# ENERGIS_DispBrd_Rack-PDU_1_0_3.net
KiCad netlist of a schematic drawn in EAGLE
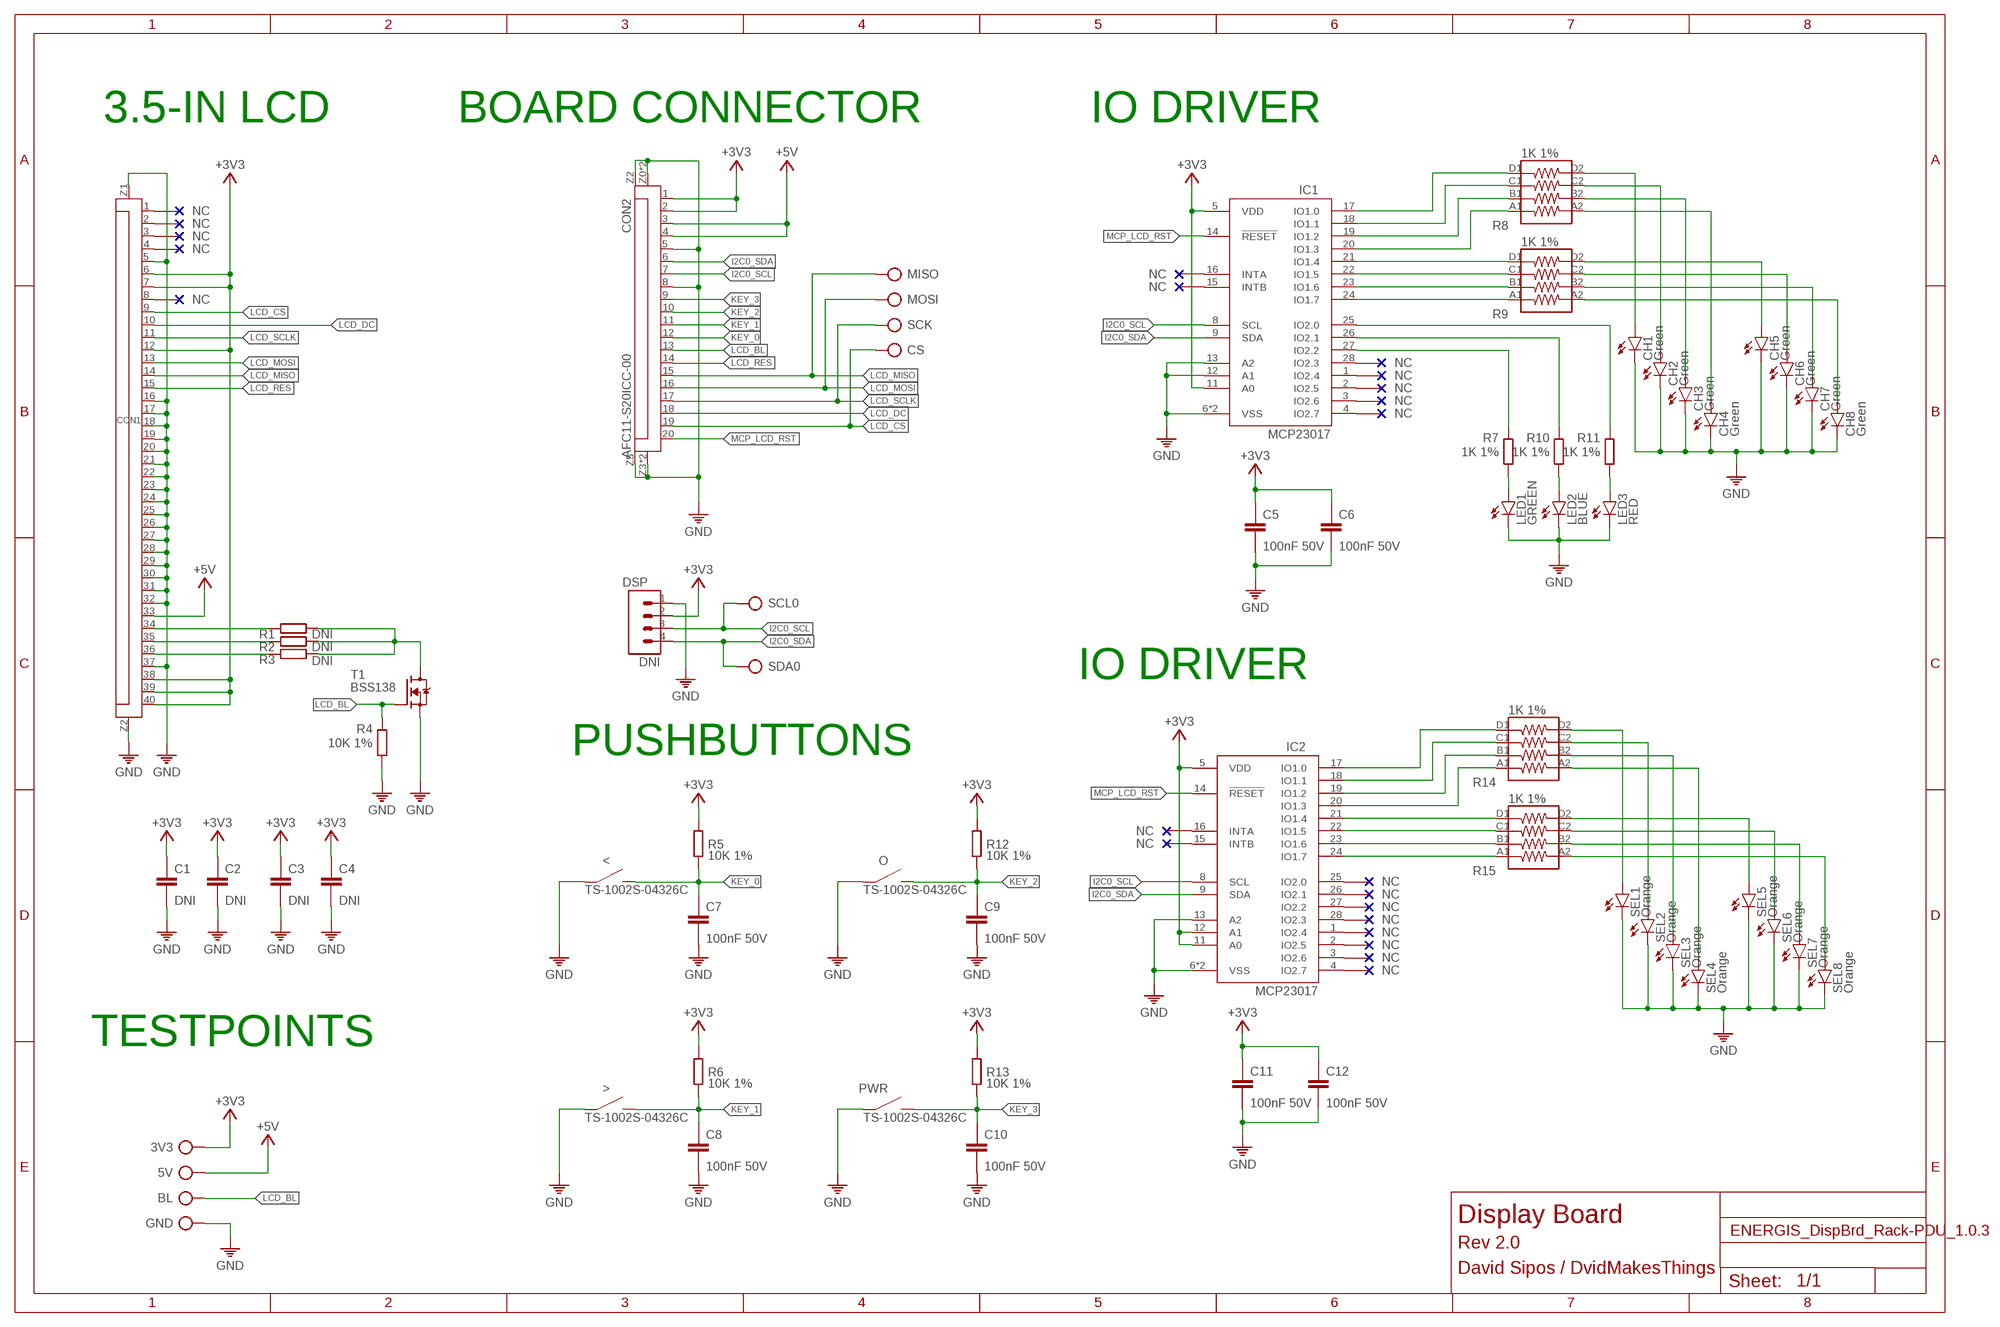
[diagram p0: schematic, sheet 1]

(export (version "E")
  (design (tool "Eeschema 10.0.6"))
  (components
    (comp (ref "3V3") (value "TP") (footprint "eagle-import:TP") (libsource (lib "eagle-import") (part "TP")))
    (comp (ref "5V") (value "TP") (footprint "eagle-import:TP") (libsource (lib "eagle-import") (part "TP")))
    (comp (ref "<")
      (value "TS-1002S-04326C")
      (footprint "eagle-import:PUSHBUTTON-6X6")
      (fields (field (name "LCSC_PART") "C455108"))
      (libsource (lib "eagle-import") (part "SWITCH6X6-SHORT"))
    )
    (comp (ref ">")
      (value "TS-1002S-04326C")
      (footprint "eagle-import:PUSHBUTTON-6X6")
      (fields (field (name "LCSC_PART") "C455108"))
      (libsource (lib "eagle-import") (part "SWITCH6X6-SHORT"))
    )
    (comp (ref "BL") (value "TP") (footprint "eagle-import:TP") (libsource (lib "eagle-import") (part "TP")))
    (comp (ref "C1")
      (value "DNI")
      (footprint "eagle-import:C0402")
      (libsource (lib "eagle-import") (part "C-0402"))
    )
    (comp (ref "C2")
      (value "DNI")
      (footprint "eagle-import:C0402")
      (libsource (lib "eagle-import") (part "C-0402"))
    )
    (comp (ref "C3")
      (value "DNI")
      (footprint "eagle-import:C0402")
      (libsource (lib "eagle-import") (part "C-0402"))
    )
    (comp (ref "C4")
      (value "DNI")
      (footprint "eagle-import:C0402")
      (libsource (lib "eagle-import") (part "C-0402"))
    )
    (comp (ref "C5")
      (value "100nF 50V")
      (footprint "eagle-import:0402")
      (fields (field (name "LCSC_PART") "C307331"))
      (libsource (lib "eagle-import") (part "100NF-50V-0402"))
    )
    (comp (ref "C6")
      (value "100nF 50V")
      (footprint "eagle-import:0402")
      (fields (field (name "LCSC_PART") "C307331"))
      (libsource (lib "eagle-import") (part "100NF-50V-0402"))
    )
    (comp (ref "C7")
      (value "100nF 50V")
      (footprint "eagle-import:0402")
      (fields (field (name "LCSC_PART") "C307331"))
      (libsource (lib "eagle-import") (part "100NF-50V-0402"))
    )
    (comp (ref "C8")
      (value "100nF 50V")
      (footprint "eagle-import:0402")
      (fields (field (name "LCSC_PART") "C307331"))
      (libsource (lib "eagle-import") (part "100NF-50V-0402"))
    )
    (comp (ref "C9")
      (value "100nF 50V")
      (footprint "eagle-import:0402")
      (fields (field (name "LCSC_PART") "C307331"))
      (libsource (lib "eagle-import") (part "100NF-50V-0402"))
    )
    (comp (ref "C10")
      (value "100nF 50V")
      (footprint "eagle-import:0402")
      (fields (field (name "LCSC_PART") "C307331"))
      (libsource (lib "eagle-import") (part "100NF-50V-0402"))
    )
    (comp (ref "C11")
      (value "100nF 50V")
      (footprint "eagle-import:0402")
      (fields (field (name "LCSC_PART") "C307331"))
      (libsource (lib "eagle-import") (part "100NF-50V-0402"))
    )
    (comp (ref "C12")
      (value "100nF 50V")
      (footprint "eagle-import:0402")
      (fields (field (name "LCSC_PART") "C307331"))
      (libsource (lib "eagle-import") (part "100NF-50V-0402"))
    )
    (comp (ref "CH1")
      (value "Green")
      (footprint "eagle-import:LED-0805")
      (fields (field (name "LCSC_PART") "C2297"))
      (libsource (lib "eagle-import") (part "LED-GREENLED-0805"))
    )
    (comp (ref "CH2")
      (value "Green")
      (footprint "eagle-import:LED-0805")
      (fields (field (name "LCSC_PART") "C2297"))
      (libsource (lib "eagle-import") (part "LED-GREENLED-0805"))
    )
    (comp (ref "CH3")
      (value "Green")
      (footprint "eagle-import:LED-0805")
      (fields (field (name "LCSC_PART") "C2297"))
      (libsource (lib "eagle-import") (part "LED-GREENLED-0805"))
    )
    (comp (ref "CH4")
      (value "Green")
      (footprint "eagle-import:LED-0805")
      (fields (field (name "LCSC_PART") "C2297"))
      (libsource (lib "eagle-import") (part "LED-GREENLED-0805"))
    )
    (comp (ref "CH5")
      (value "Green")
      (footprint "eagle-import:LED-0805")
      (fields (field (name "LCSC_PART") "C2297"))
      (libsource (lib "eagle-import") (part "LED-GREENLED-0805"))
    )
    (comp (ref "CH6")
      (value "Green")
      (footprint "eagle-import:LED-0805")
      (fields (field (name "LCSC_PART") "C2297"))
      (libsource (lib "eagle-import") (part "LED-GREENLED-0805"))
    )
    (comp (ref "CH7")
      (value "Green")
      (footprint "eagle-import:LED-0805")
      (fields (field (name "LCSC_PART") "C2297"))
      (libsource (lib "eagle-import") (part "LED-GREENLED-0805"))
    )
    (comp (ref "CH8")
      (value "Green")
      (footprint "eagle-import:LED-0805")
      (fields (field (name "LCSC_PART") "C2297"))
      (libsource (lib "eagle-import") (part "LED-GREENLED-0805"))
    )
    (comp (ref "CON1")
      (value "DNI")
      (footprint "eagle-import:FPC40_3.5TFT")
      (libsource (lib "eagle-import") (part "FPC40-HD"))
    )
    (comp (ref "CON2")
      (value "AFC11-S20ICC-00")
      (footprint "eagle-import:FPC20")
      (fields (field (name "LCSC_PART") "C11073"))
      (libsource (lib "eagle-import") (part "AFC11-S20ICC-00"))
    )
    (comp (ref "CS") (value "TP") (footprint "eagle-import:TP") (libsource (lib "eagle-import") (part "TP")))
    (comp (ref "DSP")
      (value "DNI")
      (footprint "eagle-import:1X4")
      (libsource (lib "eagle-import") (part "CON-1X4"))
    )
    (comp (ref "GND") (value "TP") (footprint "eagle-import:TP") (libsource (lib "eagle-import") (part "TP")))
    (comp (ref "IC1")
      (value "MCP23017T-E/ML")
      (footprint "eagle-import:QFN28[6X6]ML")
      (fields (field (name "LCSC_PART") "C629439"))
      (libsource (lib "eagle-import") (part "MCP23017-E/ML"))
    )
    (comp (ref "IC2")
      (value "MCP23017T-E/ML")
      (footprint "eagle-import:QFN28[6X6]ML")
      (fields (field (name "LCSC_PART") "C629439"))
      (libsource (lib "eagle-import") (part "MCP23017-E/ML"))
    )
    (comp (ref "LED1")
      (value "GREEN")
      (footprint "eagle-import:LED3MM")
      (fields (field (name "LCSC_PART") "C414645"))
      (libsource (lib "eagle-import") (part "LED-GREEN3MM-CLEAR"))
    )
    (comp (ref "LED2")
      (value "BLUE")
      (footprint "eagle-import:LED3MM")
      (fields (field (name "LCSC_PART") "C86881"))
      (libsource (lib "eagle-import") (part "LED-BLUE3MM-CLEAR"))
    )
    (comp (ref "LED3")
      (value "RED")
      (footprint "eagle-import:LED3MM")
      (fields (field (name "LCSC_PART") "C330752"))
      (libsource (lib "eagle-import") (part "LED-RED3MM-CLEAR"))
    )
    (comp (ref "MISO")
      (value "TP")
      (footprint "eagle-import:TP")
      (libsource (lib "eagle-import") (part "TP"))
    )
    (comp (ref "MOSI")
      (value "TP")
      (footprint "eagle-import:TP")
      (libsource (lib "eagle-import") (part "TP"))
    )
    (comp (ref "O")
      (value "TS-1002S-04326C")
      (footprint "eagle-import:PUSHBUTTON-6X6")
      (fields (field (name "LCSC_PART") "C455108"))
      (libsource (lib "eagle-import") (part "SWITCH6X6-SHORT"))
    )
    (comp (ref "PWR")
      (value "TS-1002S-04326C")
      (footprint "eagle-import:PUSHBUTTON-6X6")
      (fields (field (name "LCSC_PART") "C455108"))
      (libsource (lib "eagle-import") (part "SWITCH6X6-SHORT"))
    )
    (comp (ref "R1")
      (value "DNI")
      (footprint "eagle-import:0402")
      (libsource (lib "eagle-import") (part "R0402"))
    )
    (comp (ref "R2")
      (value "DNI")
      (footprint "eagle-import:0402")
      (libsource (lib "eagle-import") (part "R0402"))
    )
    (comp (ref "R3")
      (value "DNI")
      (footprint "eagle-import:0402")
      (libsource (lib "eagle-import") (part "R0402"))
    )
    (comp (ref "R4")
      (value "10K 1%")
      (footprint "eagle-import:0402")
      (fields (field (name "LCSC_PART") "C25744"))
      (libsource (lib "eagle-import") (part "10K-1%0402"))
    )
    (comp (ref "R5")
      (value "10K 1%")
      (footprint "eagle-import:0402")
      (fields (field (name "LCSC_PART") "C25744"))
      (libsource (lib "eagle-import") (part "10K-1%0402"))
    )
    (comp (ref "R6")
      (value "10K 1%")
      (footprint "eagle-import:0402")
      (fields (field (name "LCSC_PART") "C25744"))
      (libsource (lib "eagle-import") (part "10K-1%0402"))
    )
    (comp (ref "R7")
      (value "1K 1%")
      (footprint "eagle-import:0402")
      (fields (field (name "LCSC_PART") "C11702"))
      (libsource (lib "eagle-import") (part "1K-1%0402"))
    )
    (comp (ref "R8")
      (value "1K 1%")
      (footprint "eagle-import:_0603X4-1206")
      (fields (field (name "LCSC_PART") "C110021"))
      (libsource (lib "eagle-import") (part "1K-1%_ARRAY0603X4-1206"))
    )
    (comp (ref "R9")
      (value "1K 1%")
      (footprint "eagle-import:_0603X4-1206")
      (fields (field (name "LCSC_PART") "C110021"))
      (libsource (lib "eagle-import") (part "1K-1%_ARRAY0603X4-1206"))
    )
    (comp (ref "R10")
      (value "1K 1%")
      (footprint "eagle-import:0402")
      (fields (field (name "LCSC_PART") "C11702"))
      (libsource (lib "eagle-import") (part "1K-1%0402"))
    )
    (comp (ref "R11")
      (value "1K 1%")
      (footprint "eagle-import:0402")
      (fields (field (name "LCSC_PART") "C11702"))
      (libsource (lib "eagle-import") (part "1K-1%0402"))
    )
    (comp (ref "R12")
      (value "10K 1%")
      (footprint "eagle-import:0402")
      (fields (field (name "LCSC_PART") "C25744"))
      (libsource (lib "eagle-import") (part "10K-1%0402"))
    )
    (comp (ref "R13")
      (value "10K 1%")
      (footprint "eagle-import:0402")
      (fields (field (name "LCSC_PART") "C25744"))
      (libsource (lib "eagle-import") (part "10K-1%0402"))
    )
    (comp (ref "R14")
      (value "1K 1%")
      (footprint "eagle-import:_0603X4-1206")
      (fields (field (name "LCSC_PART") "C110021"))
      (libsource (lib "eagle-import") (part "1K-1%_ARRAY0603X4-1206"))
    )
    (comp (ref "R15")
      (value "1K 1%")
      (footprint "eagle-import:_0603X4-1206")
      (fields (field (name "LCSC_PART") "C110021"))
      (libsource (lib "eagle-import") (part "1K-1%_ARRAY0603X4-1206"))
    )
    (comp (ref "SCK") (value "TP") (footprint "eagle-import:TP") (libsource (lib "eagle-import") (part "TP")))
    (comp (ref "SCL0")
      (value "TP")
      (footprint "eagle-import:TP")
      (libsource (lib "eagle-import") (part "TP"))
    )
    (comp (ref "SDA0")
      (value "TP")
      (footprint "eagle-import:TP")
      (libsource (lib "eagle-import") (part "TP"))
    )
    (comp (ref "SEL1")
      (value "Orange")
      (footprint "eagle-import:LED-0805")
      (fields (field (name "LCSC_PART") "C434437"))
      (libsource (lib "eagle-import") (part "LED-ORANGELED-0805"))
    )
    (comp (ref "SEL2")
      (value "Orange")
      (footprint "eagle-import:LED-0805")
      (fields (field (name "LCSC_PART") "C434437"))
      (libsource (lib "eagle-import") (part "LED-ORANGELED-0805"))
    )
    (comp (ref "SEL3")
      (value "Orange")
      (footprint "eagle-import:LED-0805")
      (fields (field (name "LCSC_PART") "C434437"))
      (libsource (lib "eagle-import") (part "LED-ORANGELED-0805"))
    )
    (comp (ref "SEL4")
      (value "Orange")
      (footprint "eagle-import:LED-0805")
      (fields (field (name "LCSC_PART") "C434437"))
      (libsource (lib "eagle-import") (part "LED-ORANGELED-0805"))
    )
    (comp (ref "SEL5")
      (value "Orange")
      (footprint "eagle-import:LED-0805")
      (fields (field (name "LCSC_PART") "C434437"))
      (libsource (lib "eagle-import") (part "LED-ORANGELED-0805"))
    )
    (comp (ref "SEL6")
      (value "Orange")
      (footprint "eagle-import:LED-0805")
      (fields (field (name "LCSC_PART") "C434437"))
      (libsource (lib "eagle-import") (part "LED-ORANGELED-0805"))
    )
    (comp (ref "SEL7")
      (value "Orange")
      (footprint "eagle-import:LED-0805")
      (fields (field (name "LCSC_PART") "C434437"))
      (libsource (lib "eagle-import") (part "LED-ORANGELED-0805"))
    )
    (comp (ref "SEL8")
      (value "Orange")
      (footprint "eagle-import:LED-0805")
      (fields (field (name "LCSC_PART") "C434437"))
      (libsource (lib "eagle-import") (part "LED-ORANGELED-0805"))
    )
    (comp (ref "T1")
      (value "BSS138")
      (footprint "eagle-import:SOT23")
      (libsource (lib "eagle-import") (part "BSS138"))
    )
  )
  (nets
    (net (code "1") (name "+3V3") (class "Default")
      (node (ref "3V3") (pin "TP") (pinfunction "P$1_TP") (pintype "bidirectional"))
      (node (ref "C1") (pin "1") (pinfunction "1_1") (pintype "passive"))
      (node (ref "C11") (pin "1") (pinfunction "1_1") (pintype "passive"))
      (node (ref "C12") (pin "1") (pinfunction "1_1") (pintype "passive"))
      (node (ref "C2") (pin "1") (pinfunction "1_1") (pintype "passive"))
      (node (ref "C3") (pin "1") (pinfunction "1_1") (pintype "passive"))
      (node (ref "C4") (pin "1") (pinfunction "1_1") (pintype "passive"))
      (node (ref "C5") (pin "1") (pinfunction "1_1") (pintype "passive"))
      (node (ref "C6") (pin "1") (pinfunction "1_1") (pintype "passive"))
      (node (ref "CON1") (pin "12") (pinfunction "12_12") (pintype "bidirectional"))
      (node (ref "CON1") (pin "38") (pinfunction "38_38") (pintype "bidirectional"))
      (node (ref "CON1") (pin "39") (pinfunction "39_39") (pintype "bidirectional"))
      (node (ref "CON1") (pin "40") (pinfunction "40_40") (pintype "bidirectional"))
      (node (ref "CON1") (pin "6") (pinfunction "6_6") (pintype "bidirectional"))
      (node (ref "CON1") (pin "7") (pinfunction "7_7") (pintype "bidirectional"))
      (node (ref "CON2") (pin "1") (pinfunction "1_1") (pintype "bidirectional"))
      (node (ref "CON2") (pin "2") (pinfunction "2_2") (pintype "bidirectional"))
      (node (ref "DSP") (pin "2") (pinfunction "P$2_2") (pintype "bidirectional"))
      (node (ref "IC1") (pin "11") (pinfunction "A0_11") (pintype "bidirectional"))
      (node (ref "IC1") (pin "5") (pinfunction "VDD_5") (pintype "bidirectional"))
      (node (ref "IC2") (pin "11") (pinfunction "A0_11") (pintype "bidirectional"))
      (node (ref "IC2") (pin "12") (pinfunction "A1_12") (pintype "bidirectional"))
      (node (ref "IC2") (pin "5") (pinfunction "VDD_5") (pintype "bidirectional"))
      (node (ref "R12") (pin "1") (pinfunction "1_1") (pintype "passive"))
      (node (ref "R13") (pin "1") (pinfunction "1_1") (pintype "passive"))
      (node (ref "R5") (pin "1") (pinfunction "1_1") (pintype "passive"))
      (node (ref "R6") (pin "1") (pinfunction "1_1") (pintype "passive"))
    )
    (net (code "2") (name "+5V") (class "Default")
      (node (ref "5V") (pin "TP") (pinfunction "P$1_TP") (pintype "bidirectional"))
      (node (ref "CON1") (pin "33") (pinfunction "33_33") (pintype "bidirectional"))
      (node (ref "CON2") (pin "3") (pinfunction "3_3") (pintype "bidirectional"))
      (node (ref "CON2") (pin "4") (pinfunction "4_4") (pintype "bidirectional"))
    )
    (net (code "3") (name "GND") (class "Default")
      (node (ref "<") (pin "1") (pinfunction "P$1_1") (pintype "bidirectional"))
      (node (ref "<") (pin "2") (pinfunction "P$1_2") (pintype "bidirectional"))
      (node (ref ">") (pin "1") (pinfunction "P$1_1") (pintype "bidirectional"))
      (node (ref ">") (pin "2") (pinfunction "P$1_2") (pintype "bidirectional"))
      (node (ref "C1") (pin "2") (pinfunction "2_2") (pintype "passive"))
      (node (ref "C10") (pin "2") (pinfunction "2_2") (pintype "passive"))
      (node (ref "C11") (pin "2") (pinfunction "2_2") (pintype "passive"))
      (node (ref "C12") (pin "2") (pinfunction "2_2") (pintype "passive"))
      (node (ref "C2") (pin "2") (pinfunction "2_2") (pintype "passive"))
      (node (ref "C3") (pin "2") (pinfunction "2_2") (pintype "passive"))
      (node (ref "C4") (pin "2") (pinfunction "2_2") (pintype "passive"))
      (node (ref "C5") (pin "2") (pinfunction "2_2") (pintype "passive"))
      (node (ref "C6") (pin "2") (pinfunction "2_2") (pintype "passive"))
      (node (ref "C7") (pin "2") (pinfunction "2_2") (pintype "passive"))
      (node (ref "C8") (pin "2") (pinfunction "2_2") (pintype "passive"))
      (node (ref "C9") (pin "2") (pinfunction "2_2") (pintype "passive"))
      (node (ref "CH1") (pin "C") (pinfunction "C_C") (pintype "passive"))
      (node (ref "CH2") (pin "C") (pinfunction "C_C") (pintype "passive"))
      (node (ref "CH3") (pin "C") (pinfunction "C_C") (pintype "passive"))
      (node (ref "CH4") (pin "C") (pinfunction "C_C") (pintype "passive"))
      (node (ref "CH5") (pin "C") (pinfunction "C_C") (pintype "passive"))
      (node (ref "CH6") (pin "C") (pinfunction "C_C") (pintype "passive"))
      (node (ref "CH7") (pin "C") (pinfunction "C_C") (pintype "passive"))
      (node (ref "CH8") (pin "C") (pinfunction "C_C") (pintype "passive"))
      (node (ref "CON1") (pin "16") (pinfunction "16_16") (pintype "bidirectional"))
      (node (ref "CON1") (pin "17") (pinfunction "17_17") (pintype "bidirectional"))
      (node (ref "CON1") (pin "18") (pinfunction "18_18") (pintype "bidirectional"))
      (node (ref "CON1") (pin "19") (pinfunction "19_19") (pintype "bidirectional"))
      (node (ref "CON1") (pin "20") (pinfunction "20_20") (pintype "bidirectional"))
      (node (ref "CON1") (pin "21") (pinfunction "21_21") (pintype "bidirectional"))
      (node (ref "CON1") (pin "22") (pinfunction "22_22") (pintype "bidirectional"))
      (node (ref "CON1") (pin "23") (pinfunction "23_23") (pintype "bidirectional"))
      (node (ref "CON1") (pin "24") (pinfunction "24_24") (pintype "bidirectional"))
      (node (ref "CON1") (pin "25") (pinfunction "25_25") (pintype "bidirectional"))
      (node (ref "CON1") (pin "26") (pinfunction "26_26") (pintype "bidirectional"))
      (node (ref "CON1") (pin "27") (pinfunction "27_27") (pintype "bidirectional"))
      (node (ref "CON1") (pin "28") (pinfunction "28_28") (pintype "bidirectional"))
      (node (ref "CON1") (pin "29") (pinfunction "29_29") (pintype "bidirectional"))
      (node (ref "CON1") (pin "30") (pinfunction "30_30") (pintype "bidirectional"))
      (node (ref "CON1") (pin "31") (pinfunction "31_31") (pintype "bidirectional"))
      (node (ref "CON1") (pin "32") (pinfunction "32_32") (pintype "bidirectional"))
      (node (ref "CON1") (pin "37") (pinfunction "37_37") (pintype "bidirectional"))
      (node (ref "CON1") (pin "5") (pinfunction "5_5") (pintype "bidirectional"))
      (node (ref "CON1") (pin "Z1") (pinfunction "Z1_Z1") (pintype "bidirectional"))
      (node (ref "CON1") (pin "Z2") (pinfunction "Z2_Z2") (pintype "bidirectional"))
      (node (ref "CON2") (pin "5") (pinfunction "5_5") (pintype "bidirectional"))
      (node (ref "CON2") (pin "8") (pinfunction "8_8") (pintype "bidirectional"))
      (node (ref "CON2") (pin "Z0") (pinfunction "Z1_Z0") (pintype "bidirectional"))
      (node (ref "CON2") (pin "Z1") (pinfunction "Z1_Z1") (pintype "bidirectional"))
      (node (ref "CON2") (pin "Z2") (pinfunction "Z2_Z2") (pintype "bidirectional"))
      (node (ref "CON2") (pin "Z3") (pinfunction "Z3_Z3") (pintype "bidirectional"))
      (node (ref "CON2") (pin "Z4") (pinfunction "Z3_Z4") (pintype "bidirectional"))
      (node (ref "CON2") (pin "Z5") (pinfunction "Z4_Z5") (pintype "bidirectional"))
      (node (ref "DSP") (pin "1") (pinfunction "P$1_1") (pintype "bidirectional"))
      (node (ref "GND") (pin "TP") (pinfunction "P$1_TP") (pintype "bidirectional"))
      (node (ref "IC1") (pin "12") (pinfunction "A1_12") (pintype "bidirectional"))
      (node (ref "IC1") (pin "13") (pinfunction "A2_13") (pintype "bidirectional"))
      (node (ref "IC1") (pin "6") (pinfunction "VSS_6") (pintype "bidirectional"))
      (node (ref "IC1") (pin "PAD") (pinfunction "VSS_PAD") (pintype "bidirectional"))
      (node (ref "IC2") (pin "13") (pinfunction "A2_13") (pintype "bidirectional"))
      (node (ref "IC2") (pin "6") (pinfunction "VSS_6") (pintype "bidirectional"))
      (node (ref "IC2") (pin "PAD") (pinfunction "VSS_PAD") (pintype "bidirectional"))
      (node (ref "LED1") (pin "K") (pinfunction "C_K") (pintype "passive"))
      (node (ref "LED2") (pin "K") (pinfunction "C_K") (pintype "passive"))
      (node (ref "LED3") (pin "K") (pinfunction "C_K") (pintype "passive"))
      (node (ref "O") (pin "1") (pinfunction "P$1_1") (pintype "bidirectional"))
      (node (ref "O") (pin "2") (pinfunction "P$1_2") (pintype "bidirectional"))
      (node (ref "PWR") (pin "1") (pinfunction "P$1_1") (pintype "bidirectional"))
      (node (ref "PWR") (pin "2") (pinfunction "P$1_2") (pintype "bidirectional"))
      (node (ref "R4") (pin "2") (pinfunction "2_2") (pintype "passive"))
      (node (ref "SEL1") (pin "C") (pinfunction "C_C") (pintype "passive"))
      (node (ref "SEL2") (pin "C") (pinfunction "C_C") (pintype "passive"))
      (node (ref "SEL3") (pin "C") (pinfunction "C_C") (pintype "passive"))
      (node (ref "SEL4") (pin "C") (pinfunction "C_C") (pintype "passive"))
      (node (ref "SEL5") (pin "C") (pinfunction "C_C") (pintype "passive"))
      (node (ref "SEL6") (pin "C") (pinfunction "C_C") (pintype "passive"))
      (node (ref "SEL7") (pin "C") (pinfunction "C_C") (pintype "passive"))
      (node (ref "SEL8") (pin "C") (pinfunction "C_C") (pintype "passive"))
      (node (ref "T1") (pin "2") (pinfunction "S_2") (pintype "passive"))
    )
    (net (code "4") (name "I2C0_SCL") (class "Default")
      (node (ref "CON2") (pin "7") (pinfunction "7_7") (pintype "bidirectional"))
      (node (ref "DSP") (pin "3") (pinfunction "P$3_3") (pintype "bidirectional"))
      (node (ref "IC1") (pin "8") (pinfunction "SCL_8") (pintype "bidirectional"))
      (node (ref "IC2") (pin "8") (pinfunction "SCL_8") (pintype "bidirectional"))
      (node (ref "SCL0") (pin "TP") (pinfunction "P$1_TP") (pintype "bidirectional"))
    )
    (net (code "5") (name "I2C0_SDA") (class "Default")
      (node (ref "CON2") (pin "6") (pinfunction "6_6") (pintype "bidirectional"))
      (node (ref "DSP") (pin "4") (pinfunction "P$4_4") (pintype "bidirectional"))
      (node (ref "IC1") (pin "9") (pinfunction "SDA_9") (pintype "bidirectional"))
      (node (ref "IC2") (pin "9") (pinfunction "SDA_9") (pintype "bidirectional"))
      (node (ref "SDA0") (pin "TP") (pinfunction "P$1_TP") (pintype "bidirectional"))
    )
    (net (code "6") (name "KEY_0") (class "Default")
      (node (ref "<") (pin "3") (pinfunction "P$2_3") (pintype "bidirectional"))
      (node (ref "<") (pin "4") (pinfunction "P$2_4") (pintype "bidirectional"))
      (node (ref "C7") (pin "1") (pinfunction "1_1") (pintype "passive"))
      (node (ref "CON2") (pin "12") (pinfunction "12_12") (pintype "bidirectional"))
      (node (ref "R5") (pin "2") (pinfunction "2_2") (pintype "passive"))
    )
    (net (code "7") (name "KEY_1") (class "Default")
      (node (ref ">") (pin "3") (pinfunction "P$2_3") (pintype "bidirectional"))
      (node (ref ">") (pin "4") (pinfunction "P$2_4") (pintype "bidirectional"))
      (node (ref "C8") (pin "1") (pinfunction "1_1") (pintype "passive"))
      (node (ref "CON2") (pin "11") (pinfunction "11_11") (pintype "bidirectional"))
      (node (ref "R6") (pin "2") (pinfunction "2_2") (pintype "passive"))
    )
    (net (code "8") (name "KEY_2") (class "Default")
      (node (ref "C9") (pin "1") (pinfunction "1_1") (pintype "passive"))
      (node (ref "CON2") (pin "10") (pinfunction "10_10") (pintype "bidirectional"))
      (node (ref "O") (pin "3") (pinfunction "P$2_3") (pintype "bidirectional"))
      (node (ref "O") (pin "4") (pinfunction "P$2_4") (pintype "bidirectional"))
      (node (ref "R12") (pin "2") (pinfunction "2_2") (pintype "passive"))
    )
    (net (code "9") (name "KEY_3") (class "Default")
      (node (ref "C10") (pin "1") (pinfunction "1_1") (pintype "passive"))
      (node (ref "CON2") (pin "9") (pinfunction "9_9") (pintype "bidirectional"))
      (node (ref "PWR") (pin "3") (pinfunction "P$2_3") (pintype "bidirectional"))
      (node (ref "PWR") (pin "4") (pinfunction "P$2_4") (pintype "bidirectional"))
      (node (ref "R13") (pin "2") (pinfunction "2_2") (pintype "passive"))
    )
    (net (code "10") (name "LCD_BL") (class "Default")
      (node (ref "BL") (pin "TP") (pinfunction "P$1_TP") (pintype "bidirectional"))
      (node (ref "CON2") (pin "13") (pinfunction "13_13") (pintype "bidirectional"))
      (node (ref "R4") (pin "1") (pinfunction "1_1") (pintype "passive"))
      (node (ref "T1") (pin "1") (pinfunction "G_1") (pintype "passive"))
    )
    (net (code "11") (name "LCD_CS") (class "Default")
      (node (ref "CON1") (pin "9") (pinfunction "9_9") (pintype "bidirectional"))
      (node (ref "CON2") (pin "19") (pinfunction "19_19") (pintype "bidirectional"))
      (node (ref "CS") (pin "TP") (pinfunction "P$1_TP") (pintype "bidirectional"))
    )
    (net (code "12") (name "LCD_DC") (class "Default")
      (node (ref "CON1") (pin "10") (pinfunction "10_10") (pintype "bidirectional"))
      (node (ref "CON2") (pin "18") (pinfunction "18_18") (pintype "bidirectional"))
    )
    (net (code "13") (name "LCD_MISO") (class "Default")
      (node (ref "CON1") (pin "14") (pinfunction "14_14") (pintype "bidirectional"))
      (node (ref "CON2") (pin "15") (pinfunction "15_15") (pintype "bidirectional"))
      (node (ref "MISO") (pin "TP") (pinfunction "P$1_TP") (pintype "bidirectional"))
    )
    (net (code "14") (name "LCD_MOSI") (class "Default")
      (node (ref "CON1") (pin "13") (pinfunction "13_13") (pintype "bidirectional"))
      (node (ref "CON2") (pin "16") (pinfunction "16_16") (pintype "bidirectional"))
      (node (ref "MOSI") (pin "TP") (pinfunction "P$1_TP") (pintype "bidirectional"))
    )
    (net (code "15") (name "LCD_RES") (class "Default")
      (node (ref "CON1") (pin "15") (pinfunction "15_15") (pintype "bidirectional"))
      (node (ref "CON2") (pin "14") (pinfunction "14_14") (pintype "bidirectional"))
    )
    (net (code "16") (name "LCD_SCLK") (class "Default")
      (node (ref "CON1") (pin "11") (pinfunction "11_11") (pintype "bidirectional"))
      (node (ref "CON2") (pin "17") (pinfunction "17_17") (pintype "bidirectional"))
      (node (ref "SCK") (pin "TP") (pinfunction "P$1_TP") (pintype "bidirectional"))
    )
    (net (code "17") (name "MCP_LCD_RST") (class "Default")
      (node (ref "CON2") (pin "20") (pinfunction "20_20") (pintype "bidirectional"))
      (node (ref "IC1") (pin "14") (pinfunction "~{RESET}_14") (pintype "bidirectional"))
      (node (ref "IC2") (pin "14") (pinfunction "~{RESET}_14") (pintype "bidirectional"))
    )
    (net (code "18") (name "Net-(CON1-Pad34)") (class "Default")
      (node (ref "CON1") (pin "34") (pinfunction "34_34") (pintype "bidirectional"))
      (node (ref "R1") (pin "2") (pinfunction "2_2") (pintype "passive"))
    )
    (net (code "19") (name "Net-(CON1-Pad35)") (class "Default")
      (node (ref "CON1") (pin "35") (pinfunction "35_35") (pintype "bidirectional"))
      (node (ref "R2") (pin "2") (pinfunction "2_2") (pintype "passive"))
    )
    (net (code "20") (name "Net-(CON1-Pad36)") (class "Default")
      (node (ref "CON1") (pin "36") (pinfunction "36_36") (pintype "bidirectional"))
      (node (ref "R3") (pin "2") (pinfunction "2_2") (pintype "passive"))
    )
    (net (code "21") (name "Net-(IC1-IO1.0)") (class "Default")
      (node (ref "IC1") (pin "17") (pinfunction "IO1.0_17") (pintype "bidirectional"))
      (node (ref "R8") (pin "D1") (pinfunction "4_D1") (pintype "passive"))
    )
    (net (code "22") (name "Net-(IC1-IO1.1)") (class "Default")
      (node (ref "IC1") (pin "18") (pinfunction "IO1.1_18") (pintype "bidirectional"))
      (node (ref "R8") (pin "C1") (pinfunction "3_C1") (pintype "passive"))
    )
    (net (code "23") (name "Net-(IC1-IO1.2)") (class "Default")
      (node (ref "IC1") (pin "19") (pinfunction "IO1.2_19") (pintype "bidirectional"))
      (node (ref "R8") (pin "B1") (pinfunction "2_B1") (pintype "passive"))
    )
    (net (code "24") (name "Net-(IC1-IO1.3)") (class "Default")
      (node (ref "IC1") (pin "20") (pinfunction "IO1.3_20") (pintype "bidirectional"))
      (node (ref "R8") (pin "A1") (pinfunction "1_A1") (pintype "passive"))
    )
    (net (code "25") (name "Net-(IC1-IO1.4)") (class "Default")
      (node (ref "IC1") (pin "21") (pinfunction "IO1.4_21") (pintype "bidirectional"))
      (node (ref "R9") (pin "D1") (pinfunction "4_D1") (pintype "passive"))
    )
    (net (code "26") (name "Net-(IC1-IO1.5)") (class "Default")
      (node (ref "IC1") (pin "22") (pinfunction "IO1.5_22") (pintype "bidirectional"))
      (node (ref "R9") (pin "C1") (pinfunction "3_C1") (pintype "passive"))
    )
    (net (code "27") (name "Net-(IC1-IO1.6)") (class "Default")
      (node (ref "IC1") (pin "23") (pinfunction "IO1.6_23") (pintype "bidirectional"))
      (node (ref "R9") (pin "B1") (pinfunction "2_B1") (pintype "passive"))
    )
    (net (code "28") (name "Net-(IC1-IO1.7)") (class "Default")
      (node (ref "IC1") (pin "24") (pinfunction "IO1.7_24") (pintype "bidirectional"))
      (node (ref "R9") (pin "A1") (pinfunction "1_A1") (pintype "passive"))
    )
    (net (code "29") (name "Net-(IC1-IO2.0)") (class "Default")
      (node (ref "IC1") (pin "25") (pinfunction "IO2.0_25") (pintype "bidirectional"))
      (node (ref "R11") (pin "1") (pinfunction "1_1") (pintype "passive"))
    )
    (net (code "30") (name "Net-(IC1-IO2.1)") (class "Default")
      (node (ref "IC1") (pin "26") (pinfunction "IO2.1_26") (pintype "bidirectional"))
      (node (ref "R10") (pin "1") (pinfunction "1_1") (pintype "passive"))
    )
    (net (code "31") (name "Net-(IC1-IO2.2)") (class "Default")
      (node (ref "IC1") (pin "27") (pinfunction "IO2.2_27") (pintype "bidirectional"))
      (node (ref "R7") (pin "1") (pinfunction "1_1") (pintype "passive"))
    )
    (net (code "32") (name "Net-(IC2-IO1.0)") (class "Default")
      (node (ref "IC2") (pin "17") (pinfunction "IO1.0_17") (pintype "bidirectional"))
      (node (ref "R14") (pin "D1") (pinfunction "4_D1") (pintype "passive"))
    )
    (net (code "33") (name "Net-(IC2-IO1.1)") (class "Default")
      (node (ref "IC2") (pin "18") (pinfunction "IO1.1_18") (pintype "bidirectional"))
      (node (ref "R14") (pin "C1") (pinfunction "3_C1") (pintype "passive"))
    )
    (net (code "34") (name "Net-(IC2-IO1.2)") (class "Default")
      (node (ref "IC2") (pin "19") (pinfunction "IO1.2_19") (pintype "bidirectional"))
      (node (ref "R14") (pin "B1") (pinfunction "2_B1") (pintype "passive"))
    )
    (net (code "35") (name "Net-(IC2-IO1.3)") (class "Default")
      (node (ref "IC2") (pin "20") (pinfunction "IO1.3_20") (pintype "bidirectional"))
      (node (ref "R14") (pin "A1") (pinfunction "1_A1") (pintype "passive"))
    )
    (net (code "36") (name "Net-(IC2-IO1.4)") (class "Default")
      (node (ref "IC2") (pin "21") (pinfunction "IO1.4_21") (pintype "bidirectional"))
      (node (ref "R15") (pin "D1") (pinfunction "4_D1") (pintype "passive"))
    )
    (net (code "37") (name "Net-(IC2-IO1.5)") (class "Default")
      (node (ref "IC2") (pin "22") (pinfunction "IO1.5_22") (pintype "bidirectional"))
      (node (ref "R15") (pin "C1") (pinfunction "3_C1") (pintype "passive"))
    )
    (net (code "38") (name "Net-(IC2-IO1.6)") (class "Default")
      (node (ref "IC2") (pin "23") (pinfunction "IO1.6_23") (pintype "bidirectional"))
      (node (ref "R15") (pin "B1") (pinfunction "2_B1") (pintype "passive"))
    )
    (net (code "39") (name "Net-(IC2-IO1.7)") (class "Default")
      (node (ref "IC2") (pin "24") (pinfunction "IO1.7_24") (pintype "bidirectional"))
      (node (ref "R15") (pin "A1") (pinfunction "1_A1") (pintype "passive"))
    )
    (net (code "40") (name "Net-(LED1-PadA)") (class "Default")
      (node (ref "LED1") (pin "A") (pinfunction "A_A") (pintype "passive"))
      (node (ref "R7") (pin "2") (pinfunction "2_2") (pintype "passive"))
    )
    (net (code "41") (name "Net-(LED2-PadA)") (class "Default")
      (node (ref "LED2") (pin "A") (pinfunction "A_A") (pintype "passive"))
      (node (ref "R10") (pin "2") (pinfunction "2_2") (pintype "passive"))
    )
    (net (code "42") (name "Net-(LED3-PadA)") (class "Default")
      (node (ref "LED3") (pin "A") (pinfunction "A_A") (pintype "passive"))
      (node (ref "R11") (pin "2") (pinfunction "2_2") (pintype "passive"))
    )
    (net (code "43") (name "Net-(R8-5)") (class "Default")
      (node (ref "CH1") (pin "A") (pinfunction "A_A") (pintype "passive"))
      (node (ref "R8") (pin "D2") (pinfunction "5_D2") (pintype "passive"))
    )
    (net (code "44") (name "Net-(R8-6)") (class "Default")
      (node (ref "CH2") (pin "A") (pinfunction "A_A") (pintype "passive"))
      (node (ref "R8") (pin "C2") (pinfunction "6_C2") (pintype "passive"))
    )
    (net (code "45") (name "Net-(R8-7)") (class "Default")
      (node (ref "CH3") (pin "A") (pinfunction "A_A") (pintype "passive"))
      (node (ref "R8") (pin "B2") (pinfunction "7_B2") (pintype "passive"))
    )
    (net (code "46") (name "Net-(R8-8)") (class "Default")
      (node (ref "CH4") (pin "A") (pinfunction "A_A") (pintype "passive"))
      (node (ref "R8") (pin "A2") (pinfunction "8_A2") (pintype "passive"))
    )
    (net (code "47") (name "Net-(R9-5)") (class "Default")
      (node (ref "CH5") (pin "A") (pinfunction "A_A") (pintype "passive"))
      (node (ref "R9") (pin "D2") (pinfunction "5_D2") (pintype "passive"))
    )
    (net (code "48") (name "Net-(R9-6)") (class "Default")
      (node (ref "CH6") (pin "A") (pinfunction "A_A") (pintype "passive"))
      (node (ref "R9") (pin "C2") (pinfunction "6_C2") (pintype "passive"))
    )
    (net (code "49") (name "Net-(R9-7)") (class "Default")
      (node (ref "CH7") (pin "A") (pinfunction "A_A") (pintype "passive"))
      (node (ref "R9") (pin "B2") (pinfunction "7_B2") (pintype "passive"))
    )
    (net (code "50") (name "Net-(R9-8)") (class "Default")
      (node (ref "CH8") (pin "A") (pinfunction "A_A") (pintype "passive"))
      (node (ref "R9") (pin "A2") (pinfunction "8_A2") (pintype "passive"))
    )
    (net (code "51") (name "Net-(R14-5)") (class "Default")
      (node (ref "R14") (pin "D2") (pinfunction "5_D2") (pintype "passive"))
      (node (ref "SEL1") (pin "A") (pinfunction "A_A") (pintype "passive"))
    )
    (net (code "52") (name "Net-(R14-6)") (class "Default")
      (node (ref "R14") (pin "C2") (pinfunction "6_C2") (pintype "passive"))
      (node (ref "SEL2") (pin "A") (pinfunction "A_A") (pintype "passive"))
    )
    (net (code "53") (name "Net-(R14-7)") (class "Default")
      (node (ref "R14") (pin "B2") (pinfunction "7_B2") (pintype "passive"))
      (node (ref "SEL3") (pin "A") (pinfunction "A_A") (pintype "passive"))
    )
    (net (code "54") (name "Net-(R14-8)") (class "Default")
      (node (ref "R14") (pin "A2") (pinfunction "8_A2") (pintype "passive"))
      (node (ref "SEL4") (pin "A") (pinfunction "A_A") (pintype "passive"))
    )
    (net (code "55") (name "Net-(R15-5)") (class "Default")
      (node (ref "R15") (pin "D2") (pinfunction "5_D2") (pintype "passive"))
      (node (ref "SEL5") (pin "A") (pinfunction "A_A") (pintype "passive"))
    )
    (net (code "56") (name "Net-(R15-6)") (class "Default")
      (node (ref "R15") (pin "C2") (pinfunction "6_C2") (pintype "passive"))
      (node (ref "SEL6") (pin "A") (pinfunction "A_A") (pintype "passive"))
    )
    (net (code "57") (name "Net-(R15-7)") (class "Default")
      (node (ref "R15") (pin "B2") (pinfunction "7_B2") (pintype "passive"))
      (node (ref "SEL7") (pin "A") (pinfunction "A_A") (pintype "passive"))
    )
    (net (code "58") (name "Net-(R15-8)") (class "Default")
      (node (ref "R15") (pin "A2") (pinfunction "8_A2") (pintype "passive"))
      (node (ref "SEL8") (pin "A") (pinfunction "A_A") (pintype "passive"))
    )
    (net (code "59") (name "Net-(T1-D)") (class "Default")
      (node (ref "R1") (pin "1") (pinfunction "1_1") (pintype "passive"))
      (node (ref "R2") (pin "1") (pinfunction "1_1") (pintype "passive"))
      (node (ref "R3") (pin "1") (pinfunction "1_1") (pintype "passive"))
      (node (ref "T1") (pin "3") (pinfunction "D_3") (pintype "passive"))
    )
    (net (code "60") (name "unconnected-(CON1-Pad1)") (class "Default")
      (node (ref "CON1") (pin "1") (pinfunction "1_1") (pintype "bidirectional"))
    )
    (net (code "61") (name "unconnected-(CON1-Pad2)") (class "Default")
      (node (ref "CON1") (pin "2") (pinfunction "2_2") (pintype "bidirectional"))
    )
    (net (code "62") (name "unconnected-(CON1-Pad3)") (class "Default")
      (node (ref "CON1") (pin "3") (pinfunction "3_3") (pintype "bidirectional"))
    )
    (net (code "63") (name "unconnected-(CON1-Pad4)") (class "Default")
      (node (ref "CON1") (pin "4") (pinfunction "4_4") (pintype "bidirectional"))
    )
    (net (code "64") (name "unconnected-(CON1-Pad8)") (class "Default")
      (node (ref "CON1") (pin "8") (pinfunction "8_8") (pintype "bidirectional"))
    )
    (net (code "65") (name "unconnected-(IC1-INTA-Pad16)") (class "Default")
      (node (ref "IC1") (pin "16") (pinfunction "INTA_16") (pintype "bidirectional"))
    )
    (net (code "66") (name "unconnected-(IC1-INTB-Pad15)") (class "Default")
      (node (ref "IC1") (pin "15") (pinfunction "INTB_15") (pintype "bidirectional"))
    )
    (net (code "67") (name "unconnected-(IC1-IO2.3-Pad28)") (class "Default")
      (node (ref "IC1") (pin "28") (pinfunction "IO2.3_28") (pintype "bidirectional"))
    )
    (net (code "68") (name "unconnected-(IC1-IO2.4-Pad1)") (class "Default")
      (node (ref "IC1") (pin "1") (pinfunction "IO2.4_1") (pintype "bidirectional"))
    )
    (net (code "69") (name "unconnected-(IC1-IO2.5-Pad2)") (class "Default")
      (node (ref "IC1") (pin "2") (pinfunction "IO2.5_2") (pintype "bidirectional"))
    )
    (net (code "70") (name "unconnected-(IC1-IO2.6-Pad3)") (class "Default")
      (node (ref "IC1") (pin "3") (pinfunction "IO2.6_3") (pintype "bidirectional"))
    )
    (net (code "71") (name "unconnected-(IC1-IO2.7-Pad4)") (class "Default")
      (node (ref "IC1") (pin "4") (pinfunction "IO2.7_4") (pintype "bidirectional"))
    )
    (net (code "72") (name "unconnected-(IC2-INTA-Pad16)") (class "Default")
      (node (ref "IC2") (pin "16") (pinfunction "INTA_16") (pintype "bidirectional"))
    )
    (net (code "73") (name "unconnected-(IC2-INTB-Pad15)") (class "Default")
      (node (ref "IC2") (pin "15") (pinfunction "INTB_15") (pintype "bidirectional"))
    )
    (net (code "74") (name "unconnected-(IC2-IO2.0-Pad25)") (class "Default")
      (node (ref "IC2") (pin "25") (pinfunction "IO2.0_25") (pintype "bidirectional"))
    )
    (net (code "75") (name "unconnected-(IC2-IO2.1-Pad26)") (class "Default")
      (node (ref "IC2") (pin "26") (pinfunction "IO2.1_26") (pintype "bidirectional"))
    )
    (net (code "76") (name "unconnected-(IC2-IO2.2-Pad27)") (class "Default")
      (node (ref "IC2") (pin "27") (pinfunction "IO2.2_27") (pintype "bidirectional"))
    )
    (net (code "77") (name "unconnected-(IC2-IO2.3-Pad28)") (class "Default")
      (node (ref "IC2") (pin "28") (pinfunction "IO2.3_28") (pintype "bidirectional"))
    )
    (net (code "78") (name "unconnected-(IC2-IO2.4-Pad1)") (class "Default")
      (node (ref "IC2") (pin "1") (pinfunction "IO2.4_1") (pintype "bidirectional"))
    )
    (net (code "79") (name "unconnected-(IC2-IO2.5-Pad2)") (class "Default")
      (node (ref "IC2") (pin "2") (pinfunction "IO2.5_2") (pintype "bidirectional"))
    )
    (net (code "80") (name "unconnected-(IC2-IO2.6-Pad3)") (class "Default")
      (node (ref "IC2") (pin "3") (pinfunction "IO2.6_3") (pintype "bidirectional"))
    )
    (net (code "81") (name "unconnected-(IC2-IO2.7-Pad4)") (class "Default")
      (node (ref "IC2") (pin "4") (pinfunction "IO2.7_4") (pintype "bidirectional"))
    )
  )
)
